# MasterRelaySchematic.net
KiCad netlist of a schematic drawn in Altium Designer
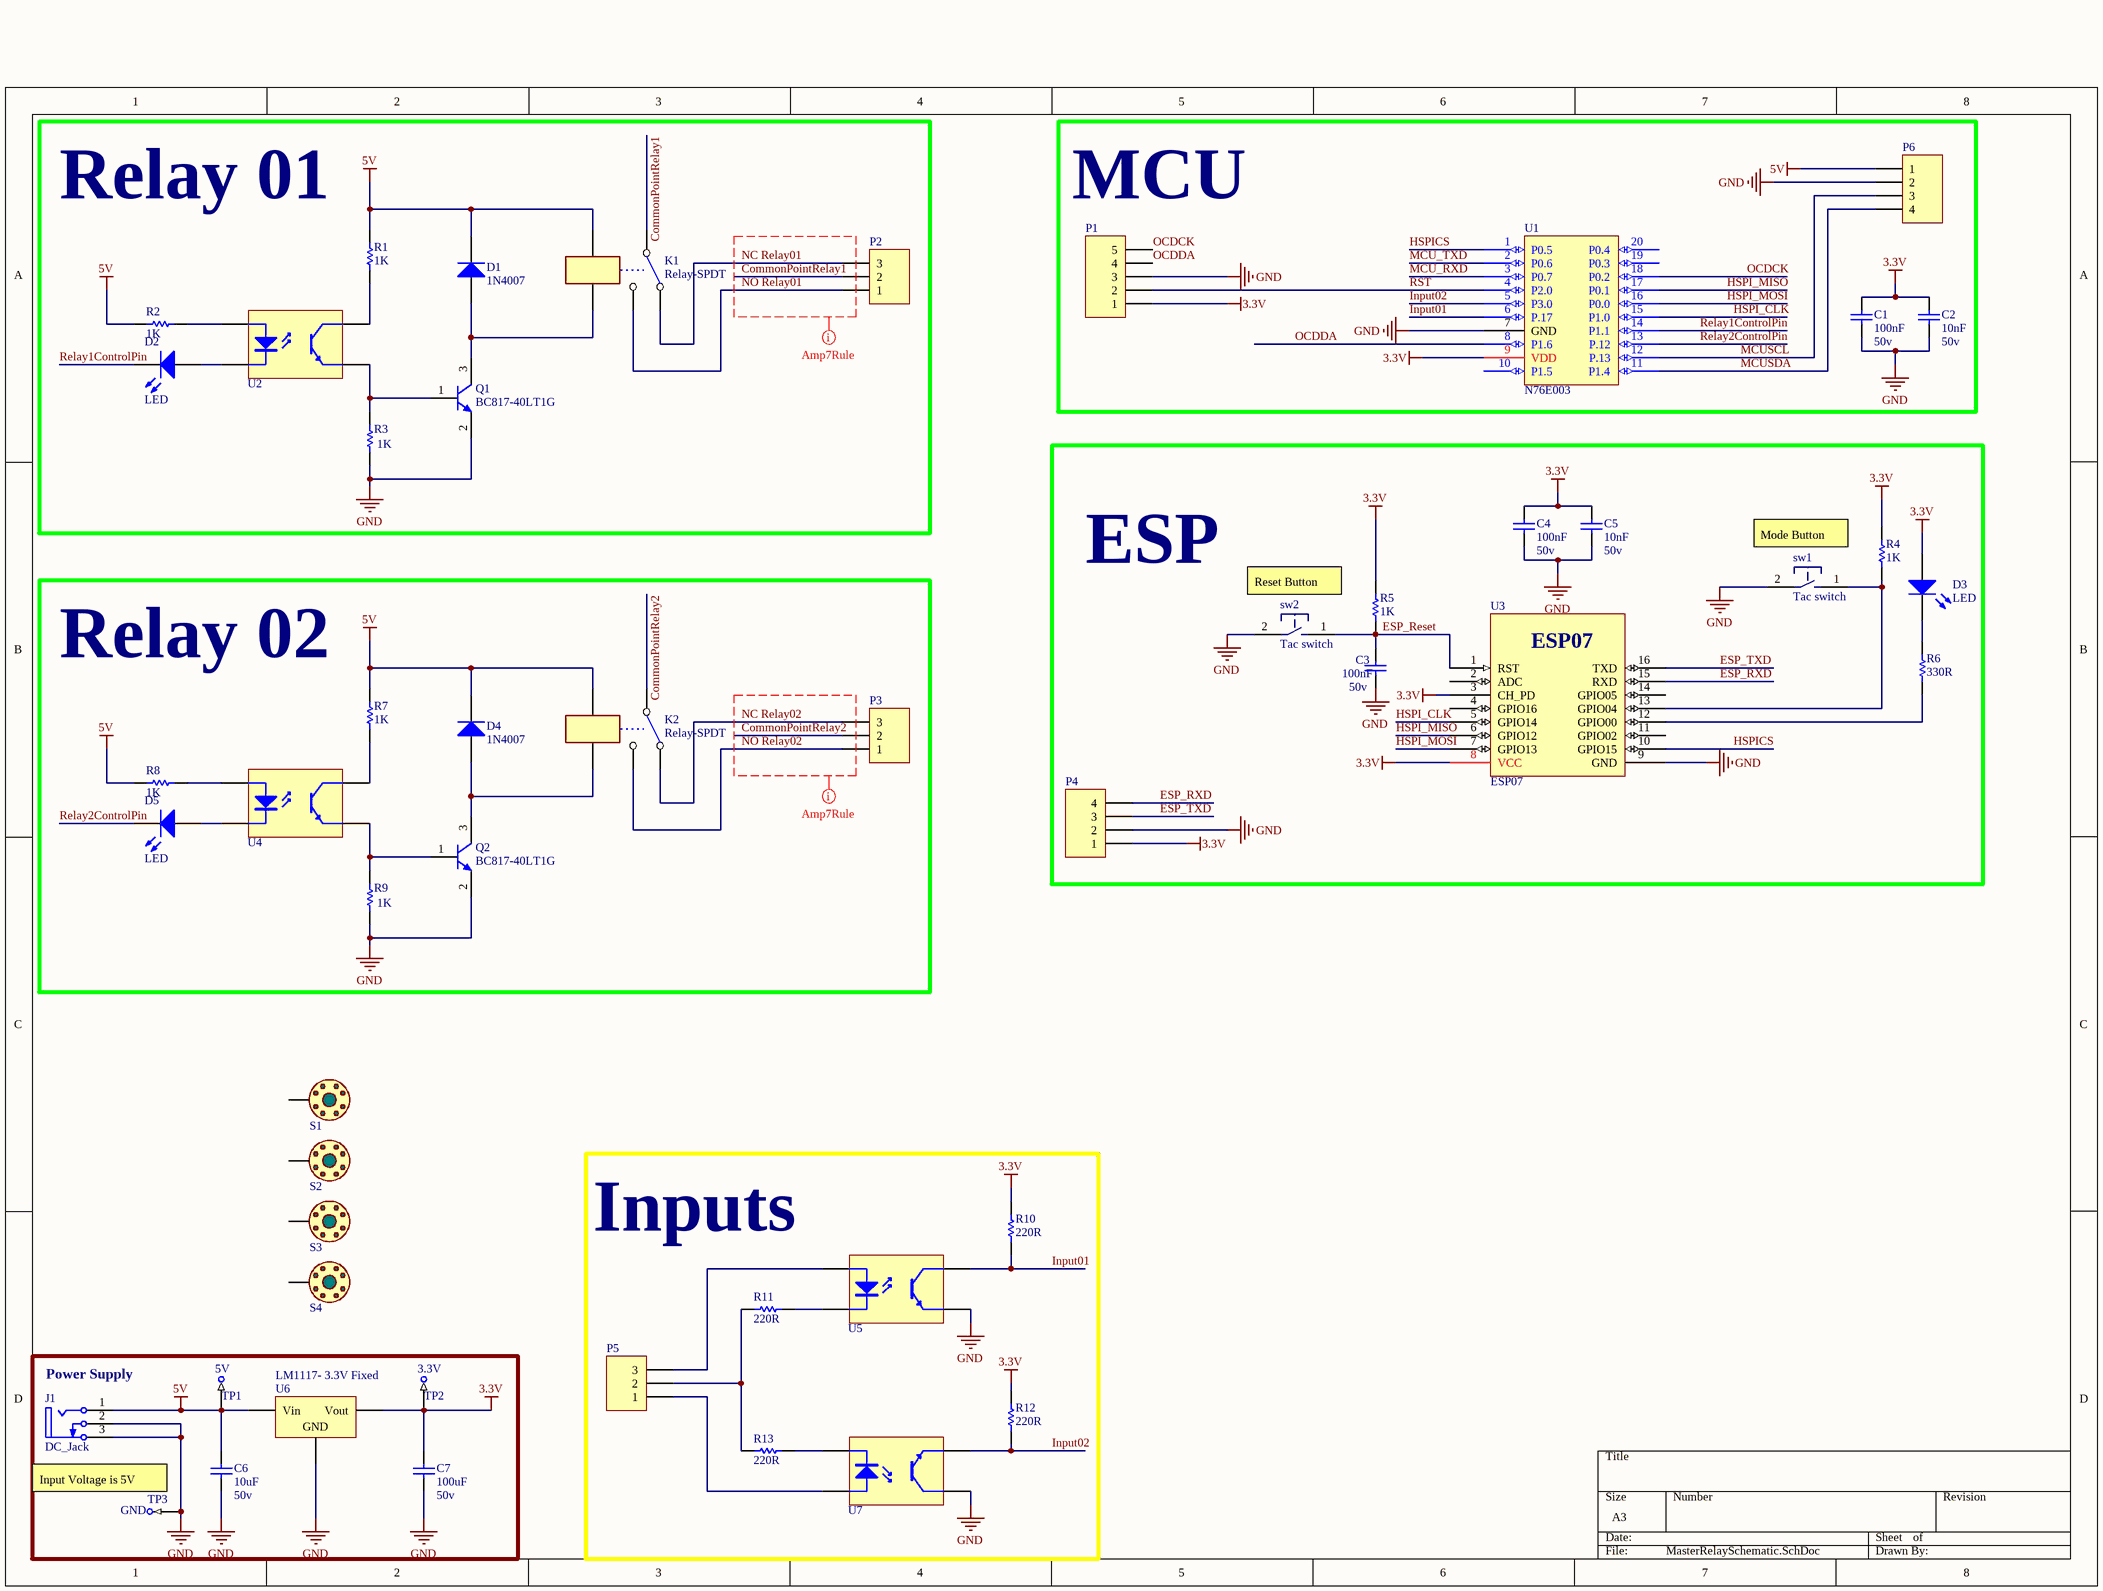
[diagram p0: MasterRelaySchematic.SchDoc]

(export (version "E")
  (design (tool "Eeschema 10.0.6"))
  (components
    (comp (ref "C1")
      (value "100nF")
      (footprint "MY_0402")
      (description "None polar capacitor")
      (fields (field (name "ASID PART NUMBER") "C-AS") (field (name "VOLTE") "50v"))
      (libsource (lib "Mylib Rev 4") (part "Cap ceramic"))
    )
    (comp (ref "C2")
      (value "10nF")
      (footprint "MY_0402")
      (description "None polar capacitor")
      (fields (field (name "ASID PART NUMBER") "C-AS") (field (name "VOLTE") "50v"))
      (libsource (lib "Mylib Rev 4") (part "Cap ceramic"))
    )
    (comp (ref "C3")
      (value "100nF")
      (footprint "MY_0805")
      (description "None polar capacitor")
      (fields (field (name "ASID PART NUMBER") "C-AS") (field (name "VOLTE") "50v"))
      (libsource (lib "Mylib Rev 4") (part "Cap ceramic"))
    )
    (comp (ref "C4")
      (value "100nF")
      (footprint "MY_0402")
      (description "None polar capacitor")
      (fields (field (name "ASID PART NUMBER") "C-AS") (field (name "VOLTE") "50v"))
      (libsource (lib "Mylib Rev 4") (part "Cap ceramic"))
    )
    (comp (ref "C5")
      (value "10nF")
      (footprint "MY_0402")
      (description "None polar capacitor")
      (fields (field (name "ASID PART NUMBER") "C-AS") (field (name "VOLTE") "50v"))
      (libsource (lib "Mylib Rev 4") (part "Cap ceramic"))
    )
    (comp (ref "C6")
      (value "10uF")
      (footprint "MY_1210")
      (description "None polar capacitor")
      (fields (field (name "ASID PART NUMBER") "C-AS") (field (name "VOLTE") "50v"))
      (libsource (lib "Mylib Rev 4") (part "Cap ceramic"))
    )
    (comp (ref "C7")
      (value "100uF")
      (footprint "MY_1210")
      (description "None polar capacitor")
      (fields (field (name "ASID PART NUMBER") "C-AS") (field (name "VOLTE") "50v"))
      (libsource (lib "Mylib Rev 4") (part "Cap ceramic"))
    )
    (comp (ref "D1")
      (value "1N4007")
      (footprint "MY_1N4007_SMD")
      (description "1 Amp Diode")
      (fields (field (name "ASID PART NUMBER") "1n4007-AS"))
      (libsource (lib "Mylib Rev 4") (part "1N4007"))
    )
    (comp (ref "D2")
      (value "LED")
      (footprint "MY_LED_0805")
      (description "Typical INFRARED GaAs LED")
      (fields (field (name "ASID PART NUMBER") "LED-AS"))
      (libsource (lib "Mylib Rev 4") (part "LED"))
    )
    (comp (ref "D3")
      (value "LED")
      (footprint "MY_LED_0805")
      (description "Typical INFRARED GaAs LED")
      (fields (field (name "ASID PART NUMBER") "LED-AS"))
      (libsource (lib "Mylib Rev 4") (part "LED"))
    )
    (comp (ref "D4")
      (value "1N4007")
      (footprint "MY_1N4007_SMD")
      (description "1 Amp Diode")
      (fields (field (name "ASID PART NUMBER") "1n4007-AS"))
      (libsource (lib "Mylib Rev 4") (part "1N4007"))
    )
    (comp (ref "D5")
      (value "LED")
      (footprint "MY_LED_0805")
      (description "Typical INFRARED GaAs LED")
      (fields (field (name "ASID PART NUMBER") "LED-AS"))
      (libsource (lib "Mylib Rev 4") (part "LED"))
    )
    (comp (ref "J1")
      (value "DC_Jack")
      (footprint "DC_Jack")
      (fields (field (name "PUBLISHER") "Altium Limited"))
      (libsource (lib "Mylib Rev 4") (part "DC_Jack"))
    )
    (comp (ref "K1")
      (value "Relay-SPDT")
      (footprint "MY_Songle")
      (description "Standard single contact relay")
      (fields (field (name "ASID PART NUMBER") "Relay-SPDT-AS"))
      (libsource (lib "Mylib Rev 4") (part "Relay-SPDT"))
    )
    (comp (ref "K2")
      (value "Relay-SPDT")
      (footprint "MY_Songle")
      (description "Standard single contact relay")
      (fields (field (name "ASID PART NUMBER") "Relay-SPDT-AS"))
      (libsource (lib "Mylib Rev 4") (part "Relay-SPDT"))
    )
    (comp (ref "P1")
      (value "Header 5")
      (footprint "My_1X05")
      (description "Header, 5-Pin")
      (fields (field (name "ASID PART NUMBER") "Header 5-AS"))
      (libsource (lib "Mylib Rev 4") (part "Header 5"))
    )
    (comp (ref "P2")
      (value "Header 3")
      (footprint "MY_MSTBA3")
      (description "Header, 3-Pin")
      (fields (field (name "ASID PART NUMBER") "Header 3-AS"))
      (libsource (lib "Mylib Rev 4") (part "Header 3"))
    )
    (comp (ref "P3")
      (value "Header 3")
      (footprint "MY_MSTBA3")
      (description "Header, 3-Pin")
      (fields (field (name "ASID PART NUMBER") "Header 3-AS"))
      (libsource (lib "Mylib Rev 4") (part "Header 3"))
    )
    (comp (ref "P4")
      (value "Header 4")
      (footprint "My_1X04")
      (description "Header, 4-Pin")
      (fields (field (name "ASID PART NUMBER") "Header 4-AS"))
      (libsource (lib "") (part "Header 4_1"))
    )
    (comp (ref "P5")
      (value "Header 3")
      (footprint "MY_MSTBA3")
      (description "Header, 3-Pin")
      (fields (field (name "ASID PART NUMBER") "Header 3-AS"))
      (libsource (lib "") (part "Header 3_1"))
    )
    (comp (ref "P6")
      (value "Header 4")
      (footprint "MY_FE04W")
      (description "Header, 4-Pin")
      (fields (field (name "ASID PART NUMBER") "Header 4-AS"))
      (libsource (lib "Mylib Rev 4") (part "Header 4"))
    )
    (comp (ref "Q1")
      (value "BC817-40LT1G")
      (footprint "ONSC-SOT-23-3-318-08_V")
      (description "General Purpose Transistor, NPN Silicon, 3-Pin SOT-23, Pb-Free, Tape and Reel")
      (fields (field (name "MANUFACTURER") "On Semiconductor"))
      (libsource (lib "Components - 22.10.19 - 22.14") (part "CMP-1048-00019-1"))
    )
    (comp (ref "Q2")
      (value "BC817-40LT1G")
      (footprint "ONSC-SOT-23-3-318-08_V")
      (description "General Purpose Transistor, NPN Silicon, 3-Pin SOT-23, Pb-Free, Tape and Reel")
      (fields (field (name "MANUFACTURER") "On Semiconductor"))
      (libsource (lib "Components - 22.10.19 - 22.14") (part "CMP-1048-00019-1"))
    )
    (comp (ref "R1")
      (value "1K")
      (footprint "MY_0805")
      (description "Standard resistor")
      (fields (field (name "ASID PART NUMBER") "Res-AS"))
      (libsource (lib "Mylib Rev 4") (part "Res"))
    )
    (comp (ref "R2")
      (value "1K")
      (footprint "MY_0805")
      (description "Standard resistor")
      (fields (field (name "ASID PART NUMBER") "Res-AS"))
      (libsource (lib "Mylib Rev 4") (part "Res"))
    )
    (comp (ref "R3")
      (value "1K")
      (footprint "MY_0805")
      (description "Standard resistor")
      (fields (field (name "ASID PART NUMBER") "Res-AS"))
      (libsource (lib "Mylib Rev 4") (part "Res"))
    )
    (comp (ref "R4")
      (value "1K")
      (footprint "MY_0805")
      (description "Standard resistor")
      (fields (field (name "ASID PART NUMBER") "Res-AS"))
      (libsource (lib "Mylib Rev 4") (part "Res"))
    )
    (comp (ref "R5")
      (value "1K")
      (footprint "MY_0805")
      (description "Standard resistor")
      (fields (field (name "ASID PART NUMBER") "Res-AS"))
      (libsource (lib "Mylib Rev 4") (part "Res"))
    )
    (comp (ref "R6")
      (value "330R")
      (footprint "MY_0805")
      (description "Standard resistor")
      (fields (field (name "ASID PART NUMBER") "Res-AS"))
      (libsource (lib "Mylib Rev 4") (part "Res"))
    )
    (comp (ref "R7")
      (value "1K")
      (footprint "MY_0805")
      (description "Standard resistor")
      (fields (field (name "ASID PART NUMBER") "Res-AS"))
      (libsource (lib "Mylib Rev 4") (part "Res"))
    )
    (comp (ref "R8")
      (value "1K")
      (footprint "MY_0805")
      (description "Standard resistor")
      (fields (field (name "ASID PART NUMBER") "Res-AS"))
      (libsource (lib "Mylib Rev 4") (part "Res"))
    )
    (comp (ref "R9")
      (value "1K")
      (footprint "MY_0805")
      (description "Standard resistor")
      (fields (field (name "ASID PART NUMBER") "Res-AS"))
      (libsource (lib "Mylib Rev 4") (part "Res"))
    )
    (comp (ref "R10")
      (value "220R")
      (footprint "MY_0805")
      (description "Standard resistor")
      (fields (field (name "ASID PART NUMBER") "Res-AS"))
      (libsource (lib "Mylib Rev 4") (part "Res"))
    )
    (comp (ref "R11")
      (value "220R")
      (footprint "MY_0805")
      (description "Standard resistor")
      (fields (field (name "ASID PART NUMBER") "Res-AS"))
      (libsource (lib "Mylib Rev 4") (part "Res"))
    )
    (comp (ref "R12")
      (value "220R")
      (footprint "MY_0805")
      (description "Standard resistor")
      (fields (field (name "ASID PART NUMBER") "Res-AS"))
      (libsource (lib "Mylib Rev 4") (part "Res"))
    )
    (comp (ref "R13")
      (value "220R")
      (footprint "MY_0805")
      (description "Standard resistor")
      (fields (field (name "ASID PART NUMBER") "Res-AS"))
      (libsource (lib "Mylib Rev 4") (part "Res"))
    )
    (comp (ref "S1")
      (value "Screw")
      (footprint "MY_PAD_3MM")
      (description "3mm Screw")
      (fields (field (name "ASID PART NUMBER") "Screw-AS"))
      (libsource (lib "Mylib Rev 4") (part "Screw"))
    )
    (comp (ref "S2")
      (value "Screw")
      (footprint "MY_PAD_3MM")
      (description "3mm Screw")
      (fields (field (name "ASID PART NUMBER") "Screw-AS"))
      (libsource (lib "Mylib Rev 4") (part "Screw"))
    )
    (comp (ref "S3")
      (value "Screw")
      (footprint "MY_PAD_3MM")
      (description "3mm Screw")
      (fields (field (name "ASID PART NUMBER") "Screw-AS"))
      (libsource (lib "Mylib Rev 4") (part "Screw"))
    )
    (comp (ref "S4")
      (value "Screw")
      (footprint "MY_PAD_3MM")
      (description "3mm Screw")
      (fields (field (name "ASID PART NUMBER") "Screw-AS"))
      (libsource (lib "Mylib Rev 4") (part "Screw"))
    )
    (comp (ref "sw1")
      (value "Tac switch")
      (footprint "MY_PB-SMD")
      (description "small tac switch")
      (fields (field (name "ASID PART NUMBER") "Tac switch-AS"))
      (libsource (lib "Mylib Rev 4") (part "Tac switch"))
    )
    (comp (ref "sw2")
      (value "Tac switch")
      (footprint "MY_PB-SMD")
      (description "small tac switch")
      (fields (field (name "ASID PART NUMBER") "Tac switch-AS"))
      (libsource (lib "Mylib Rev 4") (part "Tac switch"))
    )
    (comp (ref "TP1")
      (value "5V")
      (footprint "MY_TestPin")
      (description "Test point")
      (fields (field (name "ASID PART NUMBER") "Test Point-AS"))
      (libsource (lib "Mylib Rev 4") (part "Test Point"))
    )
    (comp (ref "TP2")
      (value "3.3V")
      (footprint "MY_TestPin")
      (description "Test point")
      (fields (field (name "ASID PART NUMBER") "Test Point-AS"))
      (libsource (lib "Mylib Rev 4") (part "Test Point"))
    )
    (comp (ref "TP3")
      (value "GND")
      (footprint "MY_TestPin")
      (description "Test point")
      (fields (field (name "ASID PART NUMBER") "Test Point-AS"))
      (libsource (lib "Mylib Rev 4") (part "Test Point"))
    )
    (comp (ref "U1") (value "N76E003") (footprint "TSSOP-20") (libsource (lib "N76E003") (part "N76E003")))
    (comp (ref "U2")
      (value "Optoisolator")
      (footprint "MY_OPTO_SMD4-7")
      (fields (field (name "ASID PART NUMBER") "Optoisolator-AS"))
      (libsource (lib "") (part "Optoisolator_1"))
    )
    (comp (ref "U3") (value "ESP07") (footprint "ESP8266 ESP_7") (libsource (lib "navid2015") (part "ESP07")))
    (comp (ref "U4")
      (value "Optoisolator")
      (footprint "MY_OPTO_SMD4-7")
      (fields (field (name "ASID PART NUMBER") "Optoisolator-AS"))
      (libsource (lib "") (part "Optoisolator_1"))
    )
    (comp (ref "U5")
      (value "Optoisolator")
      (footprint "MY_OPTO_SMD4-7")
      (fields (field (name "ASID PART NUMBER") "Optoisolator-AS"))
      (libsource (lib "") (part "Optoisolator_1"))
    )
    (comp (ref "U6")
      (value "LM1117- 3.3V Fixed")
      (footprint "MY_SOT223")
      (description "Low Drop Voltage Reg")
      (fields (field (name "ASID PART NUMBER") "LM1117-AS"))
      (libsource (lib "Mylib Rev 4") (part "LM1117"))
    )
    (comp (ref "U7")
      (value "Optoisolator")
      (footprint "MY_OPTO_SMD4-7")
      (fields (field (name "ASID PART NUMBER") "Optoisolator-AS"))
      (libsource (lib "Mylib Rev 4") (part "Optoisolator"))
    )
  )
  (nets
    (net (code "1") (name "/CommonPointRelay1") (class "Default")
      (node (ref "K1") (pin "1") (pinfunction "1_1") (pintype "passive"))
      (node (ref "P2") (pin "2") (pinfunction "2_2") (pintype "passive"))
    )
    (net (code "2") (name "/CommonPointRelay2") (class "Default")
      (node (ref "K2") (pin "1") (pinfunction "1_1") (pintype "passive"))
      (node (ref "P3") (pin "2") (pinfunction "2_2") (pintype "passive"))
    )
    (net (code "3") (name "/ESP_RXD") (class "Default")
      (node (ref "P4") (pin "4") (pinfunction "4_4") (pintype "passive"))
      (node (ref "U3") (pin "15") (pinfunction "RXD_15") (pintype "bidirectional"))
    )
    (net (code "4") (name "/ESP_Reset") (class "Default")
      (node (ref "C3") (pin "1") (pinfunction "1_1") (pintype "passive"))
      (node (ref "R5") (pin "1") (pinfunction "1_1") (pintype "passive"))
      (node (ref "U3") (pin "1") (pinfunction "RST_1") (pintype "input"))
      (node (ref "sw2") (pin "1") (pinfunction "1_1") (pintype "passive"))
    )
    (net (code "5") (name "/ESP_TXD") (class "Default")
      (node (ref "P4") (pin "3") (pinfunction "3_3") (pintype "passive"))
      (node (ref "U3") (pin "16") (pinfunction "TXD_16") (pintype "bidirectional"))
    )
    (net (code "6") (name "/HSPICS") (class "Default")
      (node (ref "U1") (pin "1") (pinfunction "P0.5_1") (pintype "bidirectional"))
      (node (ref "U3") (pin "10") (pinfunction "GPIO15_10") (pintype "bidirectional"))
    )
    (net (code "7") (name "/HSPI_CLK") (class "Default")
      (node (ref "U1") (pin "15") (pinfunction "P1.0_15") (pintype "bidirectional"))
      (node (ref "U3") (pin "5") (pinfunction "GPIO14_5") (pintype "bidirectional"))
    )
    (net (code "8") (name "/HSPI_MISO") (class "Default")
      (node (ref "U1") (pin "17") (pinfunction "P0.1_17") (pintype "bidirectional"))
      (node (ref "U3") (pin "6") (pinfunction "GPIO12_6") (pintype "bidirectional"))
    )
    (net (code "9") (name "/HSPI_MOSI") (class "Default")
      (node (ref "U1") (pin "16") (pinfunction "P0.0_16") (pintype "bidirectional"))
      (node (ref "U3") (pin "7") (pinfunction "GPIO13_7") (pintype "bidirectional"))
    )
    (net (code "10") (name "/Input01") (class "Default")
      (node (ref "R10") (pin "2") (pinfunction "2_2") (pintype "passive"))
      (node (ref "U1") (pin "6") (pinfunction "P.17_6") (pintype "bidirectional"))
      (node (ref "U5") (pin "4") (pinfunction "C_4") (pintype "passive"))
    )
    (net (code "11") (name "/Input02") (class "Default")
      (node (ref "R12") (pin "2") (pinfunction "2_2") (pintype "passive"))
      (node (ref "U1") (pin "5") (pinfunction "P3.0_5") (pintype "bidirectional"))
      (node (ref "U7") (pin "3") (pinfunction "E_3") (pintype "passive"))
    )
    (net (code "12") (name "/MCUSCL") (class "Default")
      (node (ref "P6") (pin "3") (pinfunction "3_3") (pintype "passive"))
      (node (ref "U1") (pin "12") (pinfunction "P.13_12") (pintype "bidirectional"))
    )
    (net (code "13") (name "/MCUSDA") (class "Default")
      (node (ref "P6") (pin "4") (pinfunction "4_4") (pintype "passive"))
      (node (ref "U1") (pin "11") (pinfunction "P1.4_11") (pintype "bidirectional"))
    )
    (net (code "14") (name "/MCU_RXD") (class "Default")
      (node (ref "U1") (pin "3") (pinfunction "P0.7_3") (pintype "bidirectional"))
    )
    (net (code "15") (name "/MCU_TXD") (class "Default")
      (node (ref "U1") (pin "2") (pinfunction "P0.6_2") (pintype "bidirectional"))
    )
    (net (code "16") (name "/NC Relay01") (class "Default")
      (node (ref "K1") (pin "2") (pinfunction "2_2") (pintype "passive"))
      (node (ref "P2") (pin "3") (pinfunction "3_3") (pintype "passive"))
    )
    (net (code "17") (name "/NC Relay02") (class "Default")
      (node (ref "K2") (pin "2") (pinfunction "2_2") (pintype "passive"))
      (node (ref "P3") (pin "3") (pinfunction "3_3") (pintype "passive"))
    )
    (net (code "18") (name "/NO Relay01") (class "Default")
      (node (ref "K1") (pin "3") (pinfunction "3_3") (pintype "passive"))
      (node (ref "P2") (pin "1") (pinfunction "1_1") (pintype "passive"))
    )
    (net (code "19") (name "/NO Relay02") (class "Default")
      (node (ref "K2") (pin "3") (pinfunction "3_3") (pintype "passive"))
      (node (ref "P3") (pin "1") (pinfunction "1_1") (pintype "passive"))
    )
    (net (code "20") (name "/OCDCK") (class "Default")
      (node (ref "P1") (pin "5") (pinfunction "5_5") (pintype "passive"))
      (node (ref "U1") (pin "18") (pinfunction "P0.2_18") (pintype "bidirectional"))
    )
    (net (code "21") (name "/OCDDA") (class "Default")
      (node (ref "P1") (pin "4") (pinfunction "4_4") (pintype "passive"))
      (node (ref "U1") (pin "8") (pinfunction "P1.6_8") (pintype "bidirectional"))
    )
    (net (code "22") (name "/RST") (class "Default")
      (node (ref "P1") (pin "2") (pinfunction "2_2") (pintype "passive"))
      (node (ref "U1") (pin "4") (pinfunction "P2.0_4") (pintype "bidirectional"))
    )
    (net (code "23") (name "/Relay1ControlPin") (class "Default")
      (node (ref "D2") (pin "K") (pinfunction "K_K") (pintype "passive"))
      (node (ref "U1") (pin "14") (pinfunction "P1.1_14") (pintype "bidirectional"))
    )
    (net (code "24") (name "/Relay2ControlPin") (class "Default")
      (node (ref "D5") (pin "K") (pinfunction "K_K") (pintype "passive"))
      (node (ref "U1") (pin "13") (pinfunction "P.12_13") (pintype "bidirectional"))
    )
    (net (code "25") (name "3.3V") (class "Default")
      (node (ref "C1") (pin "2") (pinfunction "2_2") (pintype "passive"))
      (node (ref "C2") (pin "2") (pinfunction "2_2") (pintype "passive"))
      (node (ref "C4") (pin "2") (pinfunction "2_2") (pintype "passive"))
      (node (ref "C5") (pin "2") (pinfunction "2_2") (pintype "passive"))
      (node (ref "C7") (pin "1") (pinfunction "1_1") (pintype "passive"))
      (node (ref "D3") (pin "A") (pinfunction "A_A") (pintype "passive"))
      (node (ref "P1") (pin "1") (pinfunction "1_1") (pintype "passive"))
      (node (ref "P4") (pin "1") (pinfunction "1_1") (pintype "passive"))
      (node (ref "R10") (pin "1") (pinfunction "1_1") (pintype "passive"))
      (node (ref "R12") (pin "1") (pinfunction "1_1") (pintype "passive"))
      (node (ref "R4") (pin "2") (pinfunction "2_2") (pintype "passive"))
      (node (ref "R5") (pin "2") (pinfunction "2_2") (pintype "passive"))
      (node (ref "TP2") (pin "1") (pinfunction "1_1") (pintype "input"))
      (node (ref "U1") (pin "9") (pinfunction "VDD_9") (pintype "power_in"))
      (node (ref "U3") (pin "3") (pinfunction "CH_PD_3") (pintype "passive"))
      (node (ref "U3") (pin "8") (pinfunction "VCC_8") (pintype "power_in"))
      (node (ref "U6") (pin "2") (pinfunction "Vout_2") (pintype "passive"))
    )
    (net (code "26") (name "5V") (class "Default")
      (node (ref "C6") (pin "1") (pinfunction "1_1") (pintype "passive"))
      (node (ref "D1") (pin "K") (pinfunction "K_K") (pintype "passive"))
      (node (ref "D4") (pin "K") (pinfunction "K_K") (pintype "passive"))
      (node (ref "J1") (pin "1") (pinfunction "VCC_1") (pintype "power_in"))
      (node (ref "K1") (pin "4") (pinfunction "4_4") (pintype "passive"))
      (node (ref "K2") (pin "4") (pinfunction "4_4") (pintype "passive"))
      (node (ref "P6") (pin "1") (pinfunction "1_1") (pintype "passive"))
      (node (ref "R1") (pin "2") (pinfunction "2_2") (pintype "passive"))
      (node (ref "R2") (pin "1") (pinfunction "1_1") (pintype "passive"))
      (node (ref "R7") (pin "2") (pinfunction "2_2") (pintype "passive"))
      (node (ref "R8") (pin "1") (pinfunction "1_1") (pintype "passive"))
      (node (ref "TP1") (pin "1") (pinfunction "1_1") (pintype "input"))
      (node (ref "U6") (pin "3") (pinfunction "Vin_3") (pintype "passive"))
    )
    (net (code "27") (name "GND") (class "Default")
      (node (ref "C1") (pin "1") (pinfunction "1_1") (pintype "passive"))
      (node (ref "C2") (pin "1") (pinfunction "1_1") (pintype "passive"))
      (node (ref "C3") (pin "2") (pinfunction "2_2") (pintype "passive"))
      (node (ref "C4") (pin "1") (pinfunction "1_1") (pintype "passive"))
      (node (ref "C5") (pin "1") (pinfunction "1_1") (pintype "passive"))
      (node (ref "C6") (pin "2") (pinfunction "2_2") (pintype "passive"))
      (node (ref "C7") (pin "2") (pinfunction "2_2") (pintype "passive"))
      (node (ref "J1") (pin "2") (pinfunction "GND_2") (pintype "power_in"))
      (node (ref "J1") (pin "3") (pinfunction "GND_3") (pintype "power_in"))
      (node (ref "P1") (pin "3") (pinfunction "3_3") (pintype "passive"))
      (node (ref "P4") (pin "2") (pinfunction "2_2") (pintype "passive"))
      (node (ref "P6") (pin "2") (pinfunction "2_2") (pintype "passive"))
      (node (ref "Q1") (pin "2") (pinfunction "E_2") (pintype "passive"))
      (node (ref "Q2") (pin "2") (pinfunction "E_2") (pintype "passive"))
      (node (ref "R3") (pin "1") (pinfunction "1_1") (pintype "passive"))
      (node (ref "R9") (pin "1") (pinfunction "1_1") (pintype "passive"))
      (node (ref "TP3") (pin "1") (pinfunction "1_1") (pintype "input"))
      (node (ref "U1") (pin "7") (pinfunction "GND_7") (pintype "power_in"))
      (node (ref "U3") (pin "9") (pinfunction "GND_9") (pintype "power_in"))
      (node (ref "U5") (pin "3") (pinfunction "E_3") (pintype "passive"))
      (node (ref "U6") (pin "1") (pinfunction "GND_1") (pintype "passive"))
      (node (ref "U7") (pin "4") (pinfunction "C_4") (pintype "passive"))
      (node (ref "sw1") (pin "2") (pinfunction "2_2") (pintype "passive"))
      (node (ref "sw2") (pin "2") (pinfunction "2_2") (pintype "passive"))
    )
    (net (code "28") (name "Net-(D3-PadK)") (class "Default")
      (node (ref "D3") (pin "K") (pinfunction "K_K") (pintype "passive"))
      (node (ref "R6") (pin "2") (pinfunction "2_2") (pintype "passive"))
    )
    (net (code "29") (name "Net-(P5-Pad2)") (class "Default")
      (node (ref "P5") (pin "2") (pinfunction "2_2") (pintype "passive"))
      (node (ref "R11") (pin "2") (pinfunction "2_2") (pintype "passive"))
      (node (ref "R13") (pin "2") (pinfunction "2_2") (pintype "passive"))
    )
    (net (code "30") (name "Net-(Q1-B)") (class "Default")
      (node (ref "Q1") (pin "1") (pinfunction "B_1") (pintype "passive"))
      (node (ref "R3") (pin "2") (pinfunction "2_2") (pintype "passive"))
      (node (ref "U2") (pin "3") (pinfunction "E_3") (pintype "passive"))
    )
    (net (code "31") (name "Net-(Q1-C)") (class "Default")
      (node (ref "D1") (pin "A") (pinfunction "A_A") (pintype "passive"))
      (node (ref "K1") (pin "5") (pinfunction "5_5") (pintype "passive"))
      (node (ref "Q1") (pin "3") (pinfunction "C_3") (pintype "passive"))
    )
    (net (code "32") (name "Net-(Q2-B)") (class "Default")
      (node (ref "Q2") (pin "1") (pinfunction "B_1") (pintype "passive"))
      (node (ref "R9") (pin "2") (pinfunction "2_2") (pintype "passive"))
      (node (ref "U4") (pin "3") (pinfunction "E_3") (pintype "passive"))
    )
    (net (code "33") (name "Net-(Q2-C)") (class "Default")
      (node (ref "D4") (pin "A") (pinfunction "A_A") (pintype "passive"))
      (node (ref "K2") (pin "5") (pinfunction "5_5") (pintype "passive"))
      (node (ref "Q2") (pin "3") (pinfunction "C_3") (pintype "passive"))
    )
    (net (code "34") (name "Net-(U2-A)") (class "Default")
      (node (ref "R2") (pin "2") (pinfunction "2_2") (pintype "passive"))
      (node (ref "U2") (pin "1") (pinfunction "A_1") (pintype "passive"))
    )
    (net (code "35") (name "Net-(U2-C)") (class "Default")
      (node (ref "R1") (pin "1") (pinfunction "1_1") (pintype "passive"))
      (node (ref "U2") (pin "4") (pinfunction "C_4") (pintype "passive"))
    )
    (net (code "36") (name "Net-(U2-K)") (class "Default")
      (node (ref "D2") (pin "A") (pinfunction "A_A") (pintype "passive"))
      (node (ref "U2") (pin "2") (pinfunction "K_2") (pintype "passive"))
    )
    (net (code "37") (name "Net-(U3-GPIO00)") (class "Default")
      (node (ref "R6") (pin "1") (pinfunction "1_1") (pintype "passive"))
      (node (ref "U3") (pin "12") (pinfunction "GPIO00_12") (pintype "bidirectional"))
    )
    (net (code "38") (name "Net-(U3-GPIO04)") (class "Default")
      (node (ref "R4") (pin "1") (pinfunction "1_1") (pintype "passive"))
      (node (ref "U3") (pin "13") (pinfunction "GPIO04_13") (pintype "bidirectional"))
      (node (ref "sw1") (pin "1") (pinfunction "1_1") (pintype "passive"))
    )
    (net (code "39") (name "Net-(U4-A)") (class "Default")
      (node (ref "R8") (pin "2") (pinfunction "2_2") (pintype "passive"))
      (node (ref "U4") (pin "1") (pinfunction "A_1") (pintype "passive"))
    )
    (net (code "40") (name "Net-(U4-C)") (class "Default")
      (node (ref "R7") (pin "1") (pinfunction "1_1") (pintype "passive"))
      (node (ref "U4") (pin "4") (pinfunction "C_4") (pintype "passive"))
    )
    (net (code "41") (name "Net-(U4-K)") (class "Default")
      (node (ref "D5") (pin "A") (pinfunction "A_A") (pintype "passive"))
      (node (ref "U4") (pin "2") (pinfunction "K_2") (pintype "passive"))
    )
    (net (code "42") (name "Net-(U5-A)") (class "Default")
      (node (ref "P5") (pin "3") (pinfunction "3_3") (pintype "passive"))
      (node (ref "U5") (pin "1") (pinfunction "A_1") (pintype "passive"))
    )
    (net (code "43") (name "Net-(U5-K)") (class "Default")
      (node (ref "R11") (pin "1") (pinfunction "1_1") (pintype "passive"))
      (node (ref "U5") (pin "2") (pinfunction "K_2") (pintype "passive"))
    )
    (net (code "44") (name "Net-(U7-A)") (class "Default")
      (node (ref "P5") (pin "1") (pinfunction "1_1") (pintype "passive"))
      (node (ref "U7") (pin "1") (pinfunction "A_1") (pintype "passive"))
    )
    (net (code "45") (name "Net-(U7-K)") (class "Default")
      (node (ref "R13") (pin "1") (pinfunction "1_1") (pintype "passive"))
      (node (ref "U7") (pin "2") (pinfunction "K_2") (pintype "passive"))
    )
    (net (code "46") (name "unconnected-(S1-Pad0)") (class "Default")
      (node (ref "S1") (pin "0") (pinfunction "0_0") (pintype "passive"))
    )
    (net (code "47") (name "unconnected-(S2-Pad0)") (class "Default")
      (node (ref "S2") (pin "0") (pinfunction "0_0") (pintype "passive"))
    )
    (net (code "48") (name "unconnected-(S3-Pad0)") (class "Default")
      (node (ref "S3") (pin "0") (pinfunction "0_0") (pintype "passive"))
    )
    (net (code "49") (name "unconnected-(S4-Pad0)") (class "Default")
      (node (ref "S4") (pin "0") (pinfunction "0_0") (pintype "passive"))
    )
    (net (code "50") (name "unconnected-(U1-P0.3-Pad19)") (class "Default")
      (node (ref "U1") (pin "19") (pinfunction "P0.3_19") (pintype "bidirectional"))
    )
    (net (code "51") (name "unconnected-(U1-P0.4-Pad20)") (class "Default")
      (node (ref "U1") (pin "20") (pinfunction "P0.4_20") (pintype "bidirectional"))
    )
    (net (code "52") (name "unconnected-(U1-P1.5-Pad10)") (class "Default")
      (node (ref "U1") (pin "10") (pinfunction "P1.5_10") (pintype "bidirectional"))
    )
    (net (code "53") (name "unconnected-(U3-ADC-Pad2)") (class "Default")
      (node (ref "U3") (pin "2") (pinfunction "ADC_2") (pintype "bidirectional"))
    )
    (net (code "54") (name "unconnected-(U3-GPIO02-Pad11)") (class "Default")
      (node (ref "U3") (pin "11") (pinfunction "GPIO02_11") (pintype "bidirectional"))
    )
    (net (code "55") (name "unconnected-(U3-GPIO05-Pad14)") (class "Default")
      (node (ref "U3") (pin "14") (pinfunction "GPIO05_14") (pintype "bidirectional"))
    )
    (net (code "56") (name "unconnected-(U3-GPIO16-Pad4)") (class "Default")
      (node (ref "U3") (pin "4") (pinfunction "GPIO16_4") (pintype "bidirectional"))
    )
  )
)
